# M_B_adapter_414_test.net
KiCad netlist of a schematic drawn in EAGLE
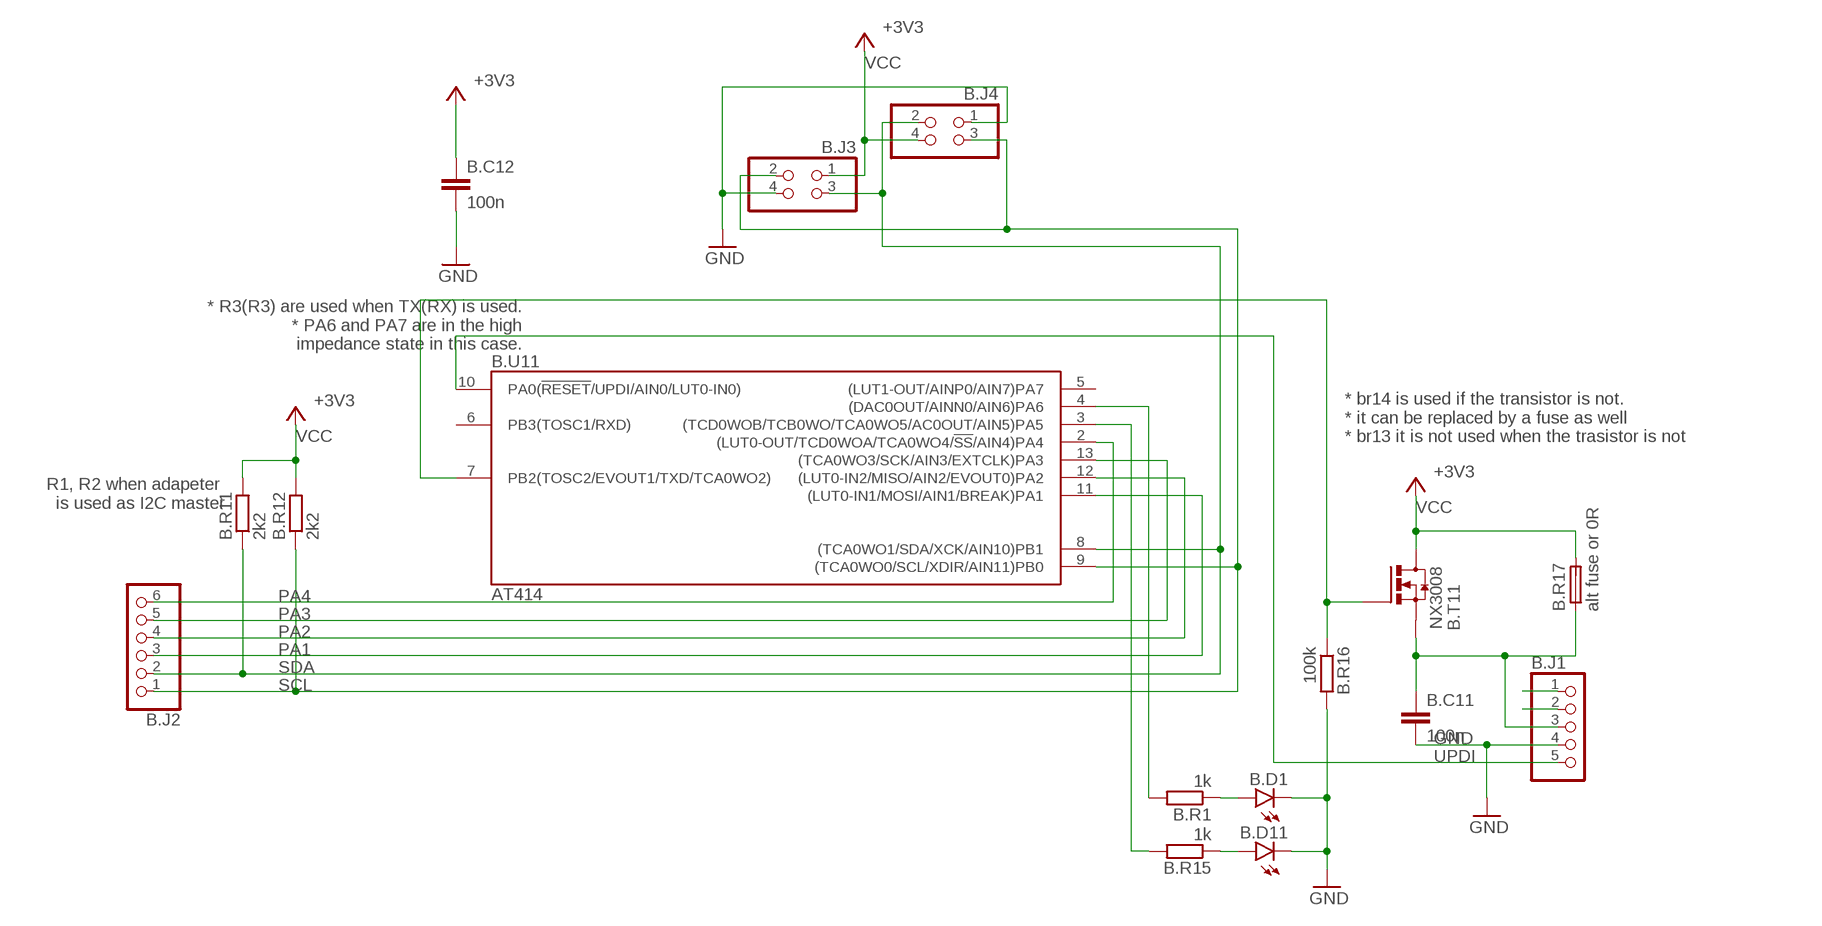
[diagram p0: schematic, sheet 1]

(export (version "E")
  (design (tool "Eeschema 10.0.6"))
  (components
    (comp (ref "B.C11")
      (value "100n")
      (footprint "eagle-import:C0603")
      (libsource (lib "eagle-import") (part "C-EUC0603"))
    )
    (comp (ref "B.C12")
      (value "100n")
      (footprint "eagle-import:C0603")
      (libsource (lib "eagle-import") (part "C-EUC0603"))
    )
    (comp (ref "B.D1")
      (value "LEDCHIP-LED0603")
      (footprint "eagle-import:CHIP-LED0603")
      (libsource (lib "eagle-import") (part "LEDCHIP-LED0603"))
    )
    (comp (ref "B.D11")
      (value "LEDCHIP-LED0603")
      (footprint "eagle-import:CHIP-LED0603")
      (libsource (lib "eagle-import") (part "LEDCHIP-LED0603"))
    )
    (comp (ref "B.J1")
      (value "PINHD-1X5")
      (footprint "eagle-import:1X05")
      (libsource (lib "eagle-import") (part "PINHD-1X5"))
    )
    (comp (ref "B.J2")
      (value "PINHD-1X6")
      (footprint "eagle-import:1X06")
      (libsource (lib "eagle-import") (part "PINHD-1X6"))
    )
    (comp (ref "B.J3")
      (value "PINHD-2X2")
      (footprint "eagle-import:2X02")
      (libsource (lib "eagle-import") (part "PINHD-2X2"))
    )
    (comp (ref "B.J4")
      (value "PINHD-2X2")
      (footprint "eagle-import:2X02")
      (libsource (lib "eagle-import") (part "PINHD-2X2"))
    )
    (comp (ref "B.R1")
      (value "1k")
      (footprint "eagle-import:R0603")
      (libsource (lib "eagle-import") (part "R-EU_R0603"))
    )
    (comp (ref "B.R11")
      (value "2k2")
      (footprint "eagle-import:R0603")
      (libsource (lib "eagle-import") (part "R-EU_R0603"))
    )
    (comp (ref "B.R12")
      (value "2k2")
      (footprint "eagle-import:R0603")
      (libsource (lib "eagle-import") (part "R-EU_R0603"))
    )
    (comp (ref "B.R15")
      (value "1k")
      (footprint "eagle-import:R0603")
      (libsource (lib "eagle-import") (part "R-EU_R0603"))
    )
    (comp (ref "B.R16")
      (value "100k")
      (footprint "eagle-import:R0603")
      (libsource (lib "eagle-import") (part "R-EU_R0603"))
    )
    (comp (ref "B.R17")
      (value "alt fuse or 0R")
      (footprint "eagle-import:FUSE")
      (libsource (lib "eagle-import") (part "FUSE"))
    )
    (comp (ref "B.T11")
      (value "NX3008")
      (footprint "eagle-import:SO23")
      (libsource (lib "eagle-import") (part "N-MOSFET"))
    )
    (comp (ref "B.U11")
      (value "AT414")
      (footprint "eagle-import:SO14")
      (libsource (lib "eagle-import") (part "ATTINY14-SSN4"))
    )
  )
  (nets
    (net (code "1") (name "+3V3") (class "Default")
      (node (ref "B.C12") (pin "1") (pinfunction "1_1") (pintype "passive"))
      (node (ref "B.J3") (pin "1") (pinfunction "1_1") (pintype "passive"))
      (node (ref "B.J4") (pin "4") (pinfunction "4_4") (pintype "passive"))
      (node (ref "B.R11") (pin "2") (pinfunction "2_2") (pintype "passive"))
      (node (ref "B.R12") (pin "2") (pinfunction "2_2") (pintype "passive"))
      (node (ref "B.R17") (pin "2") (pinfunction "2_2") (pintype "passive"))
      (node (ref "B.T11") (pin "D") (pinfunction "D_D") (pintype "passive"))
    )
    (net (code "2") (name "/PA1") (class "Default")
      (node (ref "B.J2") (pin "3") (pinfunction "3_3") (pintype "passive"))
      (node (ref "B.U11") (pin "11") (pinfunction "(LUT0-IN1/MOSI/AIN1/BREAK)PA1_11") (pintype "bidirectional"))
    )
    (net (code "3") (name "/PA2") (class "Default")
      (node (ref "B.J2") (pin "4") (pinfunction "4_4") (pintype "passive"))
      (node (ref "B.U11") (pin "12") (pinfunction "(LUT0-IN2/MISO/AIN2/EVOUT0)PA2_12") (pintype "bidirectional"))
    )
    (net (code "4") (name "/PA3") (class "Default")
      (node (ref "B.J2") (pin "5") (pinfunction "5_5") (pintype "passive"))
      (node (ref "B.U11") (pin "13") (pinfunction "(TCA0WO3/SCK/AIN3/EXTCLK)PA3_13") (pintype "bidirectional"))
    )
    (net (code "5") (name "/PA4") (class "Default")
      (node (ref "B.J2") (pin "6") (pinfunction "6_6") (pintype "passive"))
      (node (ref "B.U11") (pin "2") (pinfunction "(LUT0-OUT/TCD0WOA/TCA0WO4/~{SS}/AIN4)PA4_2") (pintype "bidirectional"))
    )
    (net (code "6") (name "/SCL") (class "Default")
      (node (ref "B.J2") (pin "1") (pinfunction "1_1") (pintype "passive"))
      (node (ref "B.J3") (pin "2") (pinfunction "2_2") (pintype "passive"))
      (node (ref "B.J4") (pin "3") (pinfunction "3_3") (pintype "passive"))
      (node (ref "B.R12") (pin "1") (pinfunction "1_1") (pintype "passive"))
      (node (ref "B.U11") (pin "9") (pinfunction "(TCA0WO0/SCL/XDIR/AIN11)PB0_9") (pintype "bidirectional"))
    )
    (net (code "7") (name "/SDA") (class "Default")
      (node (ref "B.J2") (pin "2") (pinfunction "2_2") (pintype "passive"))
      (node (ref "B.J3") (pin "3") (pinfunction "3_3") (pintype "passive"))
      (node (ref "B.J4") (pin "2") (pinfunction "2_2") (pintype "passive"))
      (node (ref "B.R11") (pin "1") (pinfunction "1_1") (pintype "passive"))
      (node (ref "B.U11") (pin "8") (pinfunction "(TCA0WO1/SDA/XCK/AIN10)PB1_8") (pintype "bidirectional"))
    )
    (net (code "8") (name "/UPDI") (class "Default")
      (node (ref "B.J1") (pin "5") (pinfunction "5_5") (pintype "passive"))
      (node (ref "B.U11") (pin "10") (pinfunction "PA0(~{RESET}/UPDI/AIN0/LUT0-IN0)_10") (pintype "bidirectional"))
    )
    (net (code "9") (name "GND") (class "Default")
      (node (ref "B.C11") (pin "2") (pinfunction "2_2") (pintype "passive"))
      (node (ref "B.C12") (pin "2") (pinfunction "2_2") (pintype "passive"))
      (node (ref "B.D1") (pin "C1") (pinfunction "C_C1") (pintype "passive"))
      (node (ref "B.D11") (pin "C1") (pinfunction "C_C1") (pintype "passive"))
      (node (ref "B.J1") (pin "4") (pinfunction "4_4") (pintype "passive"))
      (node (ref "B.J3") (pin "4") (pinfunction "4_4") (pintype "passive"))
      (node (ref "B.J4") (pin "1") (pinfunction "1_1") (pintype "passive"))
      (node (ref "B.R16") (pin "2") (pinfunction "2_2") (pintype "passive"))
    )
    (net (code "10") (name "Net-(B.C11-Pad1)") (class "Default")
      (node (ref "B.C11") (pin "1") (pinfunction "1_1") (pintype "passive"))
      (node (ref "B.J1") (pin "3") (pinfunction "3_3") (pintype "passive"))
      (node (ref "B.R17") (pin "1") (pinfunction "1_1") (pintype "passive"))
      (node (ref "B.T11") (pin "S") (pinfunction "S_S") (pintype "passive"))
    )
    (net (code "11") (name "Net-(B.D1-A)") (class "Default")
      (node (ref "B.D1") (pin "A1") (pinfunction "A_A1") (pintype "passive"))
      (node (ref "B.R1") (pin "1") (pinfunction "1_1") (pintype "passive"))
    )
    (net (code "12") (name "Net-(B.D11-A)") (class "Default")
      (node (ref "B.D11") (pin "A1") (pinfunction "A_A1") (pintype "passive"))
      (node (ref "B.R15") (pin "1") (pinfunction "1_1") (pintype "passive"))
    )
    (net (code "13") (name "Net-(B.U11A-(DAC0OUT{slash}AINN0{slash}AIN6)PA6)") (class "Default")
      (node (ref "B.R1") (pin "2") (pinfunction "2_2") (pintype "passive"))
      (node (ref "B.U11") (pin "4") (pinfunction "(DAC0OUT/AINN0/AIN6)PA6_4") (pintype "bidirectional"))
    )
    (net (code "14") (name "Net-(B.U11A-(TCD0WOB{slash}TCB0WO{slash}TCA0WO5{slash}AC0OUT{slash}AIN5)PA5)") (class "Default")
      (node (ref "B.R15") (pin "2") (pinfunction "2_2") (pintype "passive"))
      (node (ref "B.U11") (pin "3") (pinfunction "(TCD0WOB/TCB0WO/TCA0WO5/AC0OUT/AIN5)PA5_3") (pintype "bidirectional"))
    )
    (net (code "15") (name "Net-(B.U11A-PB2(TOSC2{slash}EVOUT1{slash}TXD{slash}TCA0WO2))") (class "Default")
      (node (ref "B.R16") (pin "1") (pinfunction "1_1") (pintype "passive"))
      (node (ref "B.T11") (pin "G") (pinfunction "G_G") (pintype "passive"))
      (node (ref "B.U11") (pin "7") (pinfunction "PB2(TOSC2/EVOUT1/TXD/TCA0WO2)_7") (pintype "bidirectional"))
    )
    (net (code "16") (name "unconnected-(B.J1-Pad1)") (class "Default")
      (node (ref "B.J1") (pin "1") (pinfunction "1_1") (pintype "passive"))
    )
    (net (code "17") (name "unconnected-(B.J1-Pad2)") (class "Default")
      (node (ref "B.J1") (pin "2") (pinfunction "2_2") (pintype "passive"))
    )
    (net (code "18") (name "unconnected-(B.U11A-(LUT1-OUT{slash}AINP0{slash}AIN7)PA7-Pad5)") (class "Default")
      (node (ref "B.U11") (pin "5") (pinfunction "(LUT1-OUT/AINP0/AIN7)PA7_5") (pintype "bidirectional"))
    )
    (net (code "19") (name "unconnected-(B.U11A-PB3(TOSC1{slash}RXD)-Pad6)") (class "Default")
      (node (ref "B.U11") (pin "6") (pinfunction "PB3(TOSC1/RXD)_6") (pintype "bidirectional"))
    )
  )
)
